# Interlock.net
KiCad netlist of a schematic drawn in EAGLE
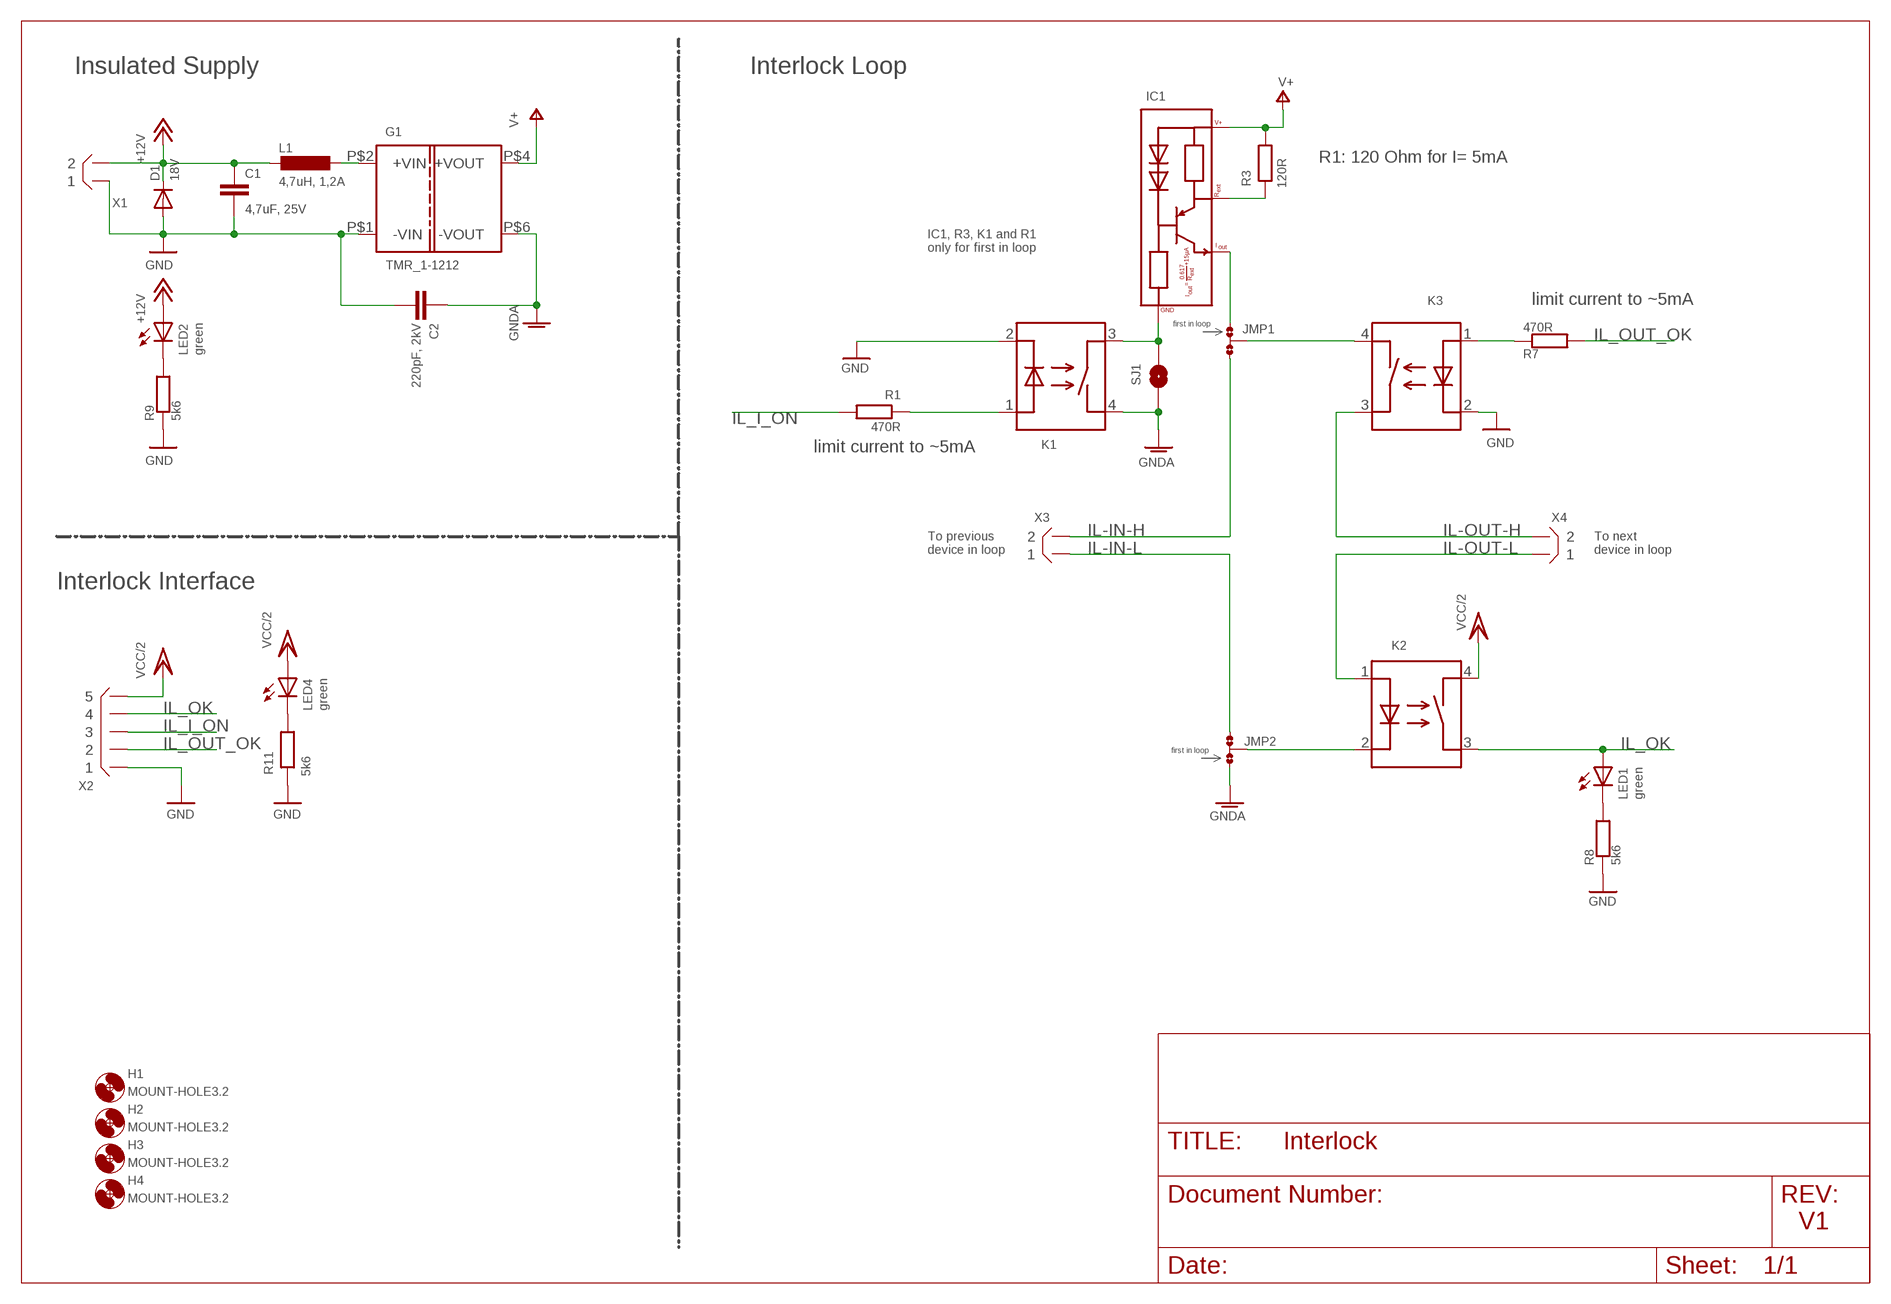
[diagram p0: schematic, sheet 1]

(export (version "E")
  (design (tool "Eeschema 10.0.6"))
  (components
    (comp (ref "C1")
      (value "4,7uF, 25V")
      (footprint "eagle-import:C0805")
      (libsource (lib "eagle-import") (part "C-EUC0805"))
    )
    (comp (ref "C2")
      (value "220pF, 2kV")
      (footprint "eagle-import:C1210_HV")
      (libsource (lib "eagle-import") (part "CC1210_HV"))
    )
    (comp (ref "D1")
      (value "18V")
      (footprint "eagle-import:DO214AA")
      (libsource (lib "eagle-import") (part "DIODE-DO214AA"))
    )
    (comp (ref "G1")
      (value "TMR_1-1212")
      (footprint "eagle-import:TMR_1-__1_")
      (libsource (lib "eagle-import") (part "TMR_1-??1?"))
    )
    (comp (ref "H1")
      (value "MOUNT-HOLE3.2")
      (footprint "eagle-import:3,2")
      (libsource (lib "eagle-import") (part "MOUNT-HOLE3.2"))
    )
    (comp (ref "H2")
      (value "MOUNT-HOLE3.2")
      (footprint "eagle-import:3,2")
      (libsource (lib "eagle-import") (part "MOUNT-HOLE3.2"))
    )
    (comp (ref "H3")
      (value "MOUNT-HOLE3.2")
      (footprint "eagle-import:3,2")
      (libsource (lib "eagle-import") (part "MOUNT-HOLE3.2"))
    )
    (comp (ref "H4")
      (value "MOUNT-HOLE3.2")
      (footprint "eagle-import:3,2")
      (libsource (lib "eagle-import") (part "MOUNT-HOLE3.2"))
    )
    (comp (ref "IC1")
      (value "PSSI2021SAY")
      (footprint "eagle-import:SOT353")
      (libsource (lib "eagle-import") (part "PSSI2021SAY"))
    )
    (comp (ref "JMP1")
      (value "0R-JUMPA")
      (footprint "eagle-import:A0R-JMP")
      (libsource (lib "eagle-import") (part "0R-JUMPA"))
    )
    (comp (ref "JMP2")
      (value "0R-JUMPA")
      (footprint "eagle-import:A0R-JMP")
      (libsource (lib "eagle-import") (part "0R-JUMPA"))
    )
    (comp (ref "K1")
      (value "ASSR-1218")
      (footprint "eagle-import:SO-4")
      (libsource (lib "eagle-import") (part "ASSR-1218"))
    )
    (comp (ref "K2")
      (value "ASSR-1218")
      (footprint "eagle-import:SO-4")
      (libsource (lib "eagle-import") (part "ASSR-1218"))
    )
    (comp (ref "K3")
      (value "ASSR-1218")
      (footprint "eagle-import:SO-4")
      (libsource (lib "eagle-import") (part "ASSR-1218"))
    )
    (comp (ref "L1")
      (value "4,7uH, 1,2A")
      (footprint "eagle-import:L3225M")
      (libsource (lib "eagle-import") (part "L-EUL3225M"))
    )
    (comp (ref "LED1")
      (value "green")
      (footprint "eagle-import:CHIPLED_0805")
      (libsource (lib "eagle-import") (part "LEDCHIPLED_0805"))
    )
    (comp (ref "LED2")
      (value "green")
      (footprint "eagle-import:CHIPLED_0805")
      (libsource (lib "eagle-import") (part "LEDCHIPLED_0805"))
    )
    (comp (ref "LED4")
      (value "green")
      (footprint "eagle-import:CHIPLED_0805")
      (libsource (lib "eagle-import") (part "LEDCHIPLED_0805"))
    )
    (comp (ref "R1")
      (value "470R")
      (footprint "eagle-import:R0805")
      (libsource (lib "eagle-import") (part "R"))
    )
    (comp (ref "R3")
      (value "120R")
      (footprint "eagle-import:R0805")
      (libsource (lib "eagle-import") (part "R"))
    )
    (comp (ref "R7")
      (value "470R")
      (footprint "eagle-import:R0805")
      (libsource (lib "eagle-import") (part "R"))
    )
    (comp (ref "R8")
      (value "5k6")
      (footprint "eagle-import:R0805")
      (libsource (lib "eagle-import") (part "R"))
    )
    (comp (ref "R9")
      (value "5k6")
      (footprint "eagle-import:R0805")
      (libsource (lib "eagle-import") (part "R"))
    )
    (comp (ref "R11")
      (value "5k6")
      (footprint "eagle-import:R0805")
      (libsource (lib "eagle-import") (part "R"))
    )
    (comp (ref "SJ1")
      (value "SOLDERJUMPERNO")
      (footprint "eagle-import:SJ_2S-NO")
      (libsource (lib "eagle-import") (part "SOLDERJUMPERNO"))
    )
    (comp (ref "X1")
      (value "B2B-XH")
      (footprint "eagle-import:B2B-XH")
      (libsource (lib "eagle-import") (part "?2B-XHB"))
    )
    (comp (ref "X2")
      (value "B5B-XH")
      (footprint "eagle-import:B5B-XH")
      (libsource (lib "eagle-import") (part "?5B-XHB"))
    )
    (comp (ref "X3")
      (value "B2B-XH")
      (footprint "eagle-import:B2B-XH")
      (libsource (lib "eagle-import") (part "?2B-XHB"))
    )
    (comp (ref "X4")
      (value "B2B-XH")
      (footprint "eagle-import:B2B-XH")
      (libsource (lib "eagle-import") (part "?2B-XHB"))
    )
  )
  (nets
    (net (code "1") (name "+12V") (class "Default")
      (node (ref "C1") (pin "1") (pinfunction "1_1") (pintype "passive"))
      (node (ref "D1") (pin "C") (pinfunction "C_C") (pintype "passive"))
      (node (ref "L1") (pin "2") (pinfunction "2_2") (pintype "passive"))
      (node (ref "LED2") (pin "A") (pinfunction "A_A") (pintype "passive"))
      (node (ref "X1") (pin "P$2") (pinfunction "2_P$2") (pintype "bidirectional"))
    )
    (net (code "2") (name "/IL-IN-H") (class "Default")
      (node (ref "JMP1") (pin "3") (pinfunction "3_3") (pintype "passive"))
      (node (ref "X3") (pin "P$2") (pinfunction "2_P$2") (pintype "bidirectional"))
    )
    (net (code "3") (name "/IL-IN-L") (class "Default")
      (node (ref "JMP2") (pin "3") (pinfunction "3_3") (pintype "passive"))
      (node (ref "X3") (pin "P$1") (pinfunction "1_P$1") (pintype "bidirectional"))
    )
    (net (code "4") (name "/IL-OUT-H") (class "Default")
      (node (ref "K3") (pin "3") (pinfunction "O2_3") (pintype "bidirectional"))
      (node (ref "X4") (pin "P$2") (pinfunction "2_P$2") (pintype "bidirectional"))
    )
    (net (code "5") (name "/IL-OUT-L") (class "Default")
      (node (ref "K2") (pin "1") (pinfunction "I+_1") (pintype "bidirectional"))
      (node (ref "X4") (pin "P$1") (pinfunction "1_P$1") (pintype "bidirectional"))
    )
    (net (code "6") (name "/IL_I_ON") (class "Default")
      (node (ref "R1") (pin "2") (pinfunction "2_2") (pintype "passive"))
      (node (ref "X2") (pin "P$3") (pinfunction "3_P$3") (pintype "bidirectional"))
    )
    (net (code "7") (name "/IL_OK") (class "Default")
      (node (ref "K2") (pin "3") (pinfunction "O2_3") (pintype "bidirectional"))
      (node (ref "LED1") (pin "A") (pinfunction "A_A") (pintype "passive"))
      (node (ref "X2") (pin "P$4") (pinfunction "4_P$4") (pintype "bidirectional"))
    )
    (net (code "8") (name "/IL_OUT_OK") (class "Default")
      (node (ref "R7") (pin "2") (pinfunction "2_2") (pintype "passive"))
      (node (ref "X2") (pin "P$2") (pinfunction "2_P$2") (pintype "bidirectional"))
    )
    (net (code "9") (name "GND") (class "Default")
      (node (ref "C1") (pin "2") (pinfunction "2_2") (pintype "passive"))
      (node (ref "C2") (pin "P$1") (pinfunction "1_P$1") (pintype "passive"))
      (node (ref "D1") (pin "A") (pinfunction "A_A") (pintype "passive"))
      (node (ref "G1") (pin "P$1") (pinfunction "-VIN_P$1") (pintype "bidirectional"))
      (node (ref "K1") (pin "2") (pinfunction "I-_2") (pintype "bidirectional"))
      (node (ref "K3") (pin "2") (pinfunction "I-_2") (pintype "bidirectional"))
      (node (ref "R11") (pin "1") (pinfunction "1_1") (pintype "passive"))
      (node (ref "R8") (pin "1") (pinfunction "1_1") (pintype "passive"))
      (node (ref "R9") (pin "1") (pinfunction "1_1") (pintype "passive"))
      (node (ref "X1") (pin "P$1") (pinfunction "1_P$1") (pintype "bidirectional"))
      (node (ref "X2") (pin "P$1") (pinfunction "1_P$1") (pintype "bidirectional"))
    )
    (net (code "10") (name "GNDA") (class "Default")
      (node (ref "C2") (pin "P$2") (pinfunction "2_P$2") (pintype "passive"))
      (node (ref "G1") (pin "P$6") (pinfunction "-VOUT_P$6") (pintype "bidirectional"))
      (node (ref "JMP2") (pin "1") (pinfunction "1_1") (pintype "passive"))
      (node (ref "K1") (pin "4") (pinfunction "O1_4") (pintype "bidirectional"))
      (node (ref "SJ1") (pin "1") (pinfunction "1_1") (pintype "passive"))
    )
    (net (code "11") (name "Net-(G1-+VIN)") (class "Default")
      (node (ref "G1") (pin "P$2") (pinfunction "+VIN_P$2") (pintype "bidirectional"))
      (node (ref "L1") (pin "1") (pinfunction "1_1") (pintype "passive"))
    )
    (net (code "12") (name "Net-(IC1-GND)") (class "Default")
      (node (ref "IC1") (pin "3") (pinfunction "GND_3") (pintype "bidirectional"))
      (node (ref "K1") (pin "3") (pinfunction "O2_3") (pintype "bidirectional"))
      (node (ref "SJ1") (pin "2") (pinfunction "2_2") (pintype "passive"))
    )
    (net (code "13") (name "Net-(IC1-IOUT)") (class "Default")
      (node (ref "IC1") (pin "2") (pinfunction "IOUT_2") (pintype "bidirectional"))
      (node (ref "JMP1") (pin "1") (pinfunction "1_1") (pintype "passive"))
    )
    (net (code "14") (name "Net-(IC1-REXT)") (class "Default")
      (node (ref "IC1") (pin "4") (pinfunction "REXT_4") (pintype "bidirectional"))
      (node (ref "R3") (pin "1") (pinfunction "1_1") (pintype "passive"))
    )
    (net (code "15") (name "Net-(K1-I+)") (class "Default")
      (node (ref "K1") (pin "1") (pinfunction "I+_1") (pintype "bidirectional"))
      (node (ref "R1") (pin "1") (pinfunction "1_1") (pintype "passive"))
    )
    (net (code "16") (name "Net-(K2-I-)") (class "Default")
      (node (ref "JMP2") (pin "2") (pinfunction "2_2") (pintype "passive"))
      (node (ref "K2") (pin "2") (pinfunction "I-_2") (pintype "bidirectional"))
    )
    (net (code "17") (name "Net-(K3-I+)") (class "Default")
      (node (ref "K3") (pin "1") (pinfunction "I+_1") (pintype "bidirectional"))
      (node (ref "R7") (pin "1") (pinfunction "1_1") (pintype "passive"))
    )
    (net (code "18") (name "Net-(K3-O1)") (class "Default")
      (node (ref "JMP1") (pin "2") (pinfunction "2_2") (pintype "passive"))
      (node (ref "K3") (pin "4") (pinfunction "O1_4") (pintype "bidirectional"))
    )
    (net (code "19") (name "Net-(LED1-PadC)") (class "Default")
      (node (ref "LED1") (pin "C") (pinfunction "C_C") (pintype "passive"))
      (node (ref "R8") (pin "2") (pinfunction "2_2") (pintype "passive"))
    )
    (net (code "20") (name "Net-(LED2-PadC)") (class "Default")
      (node (ref "LED2") (pin "C") (pinfunction "C_C") (pintype "passive"))
      (node (ref "R9") (pin "2") (pinfunction "2_2") (pintype "passive"))
    )
    (net (code "21") (name "Net-(LED4-PadC)") (class "Default")
      (node (ref "LED4") (pin "C") (pinfunction "C_C") (pintype "passive"))
      (node (ref "R11") (pin "2") (pinfunction "2_2") (pintype "passive"))
    )
    (net (code "22") (name "V+") (class "Default")
      (node (ref "G1") (pin "P$4") (pinfunction "+VOUT_P$4") (pintype "bidirectional"))
      (node (ref "IC1") (pin "5") (pinfunction "VSS_5") (pintype "bidirectional"))
      (node (ref "R3") (pin "2") (pinfunction "2_2") (pintype "passive"))
    )
    (net (code "23") (name "VCC{slash}2") (class "Default")
      (node (ref "K2") (pin "4") (pinfunction "O1_4") (pintype "bidirectional"))
      (node (ref "LED4") (pin "A") (pinfunction "A_A") (pintype "passive"))
      (node (ref "X2") (pin "P$5") (pinfunction "5_P$5") (pintype "bidirectional"))
    )
  )
)
